# store-row-block.net
KiCad netlist of a schematic drawn in EAGLE
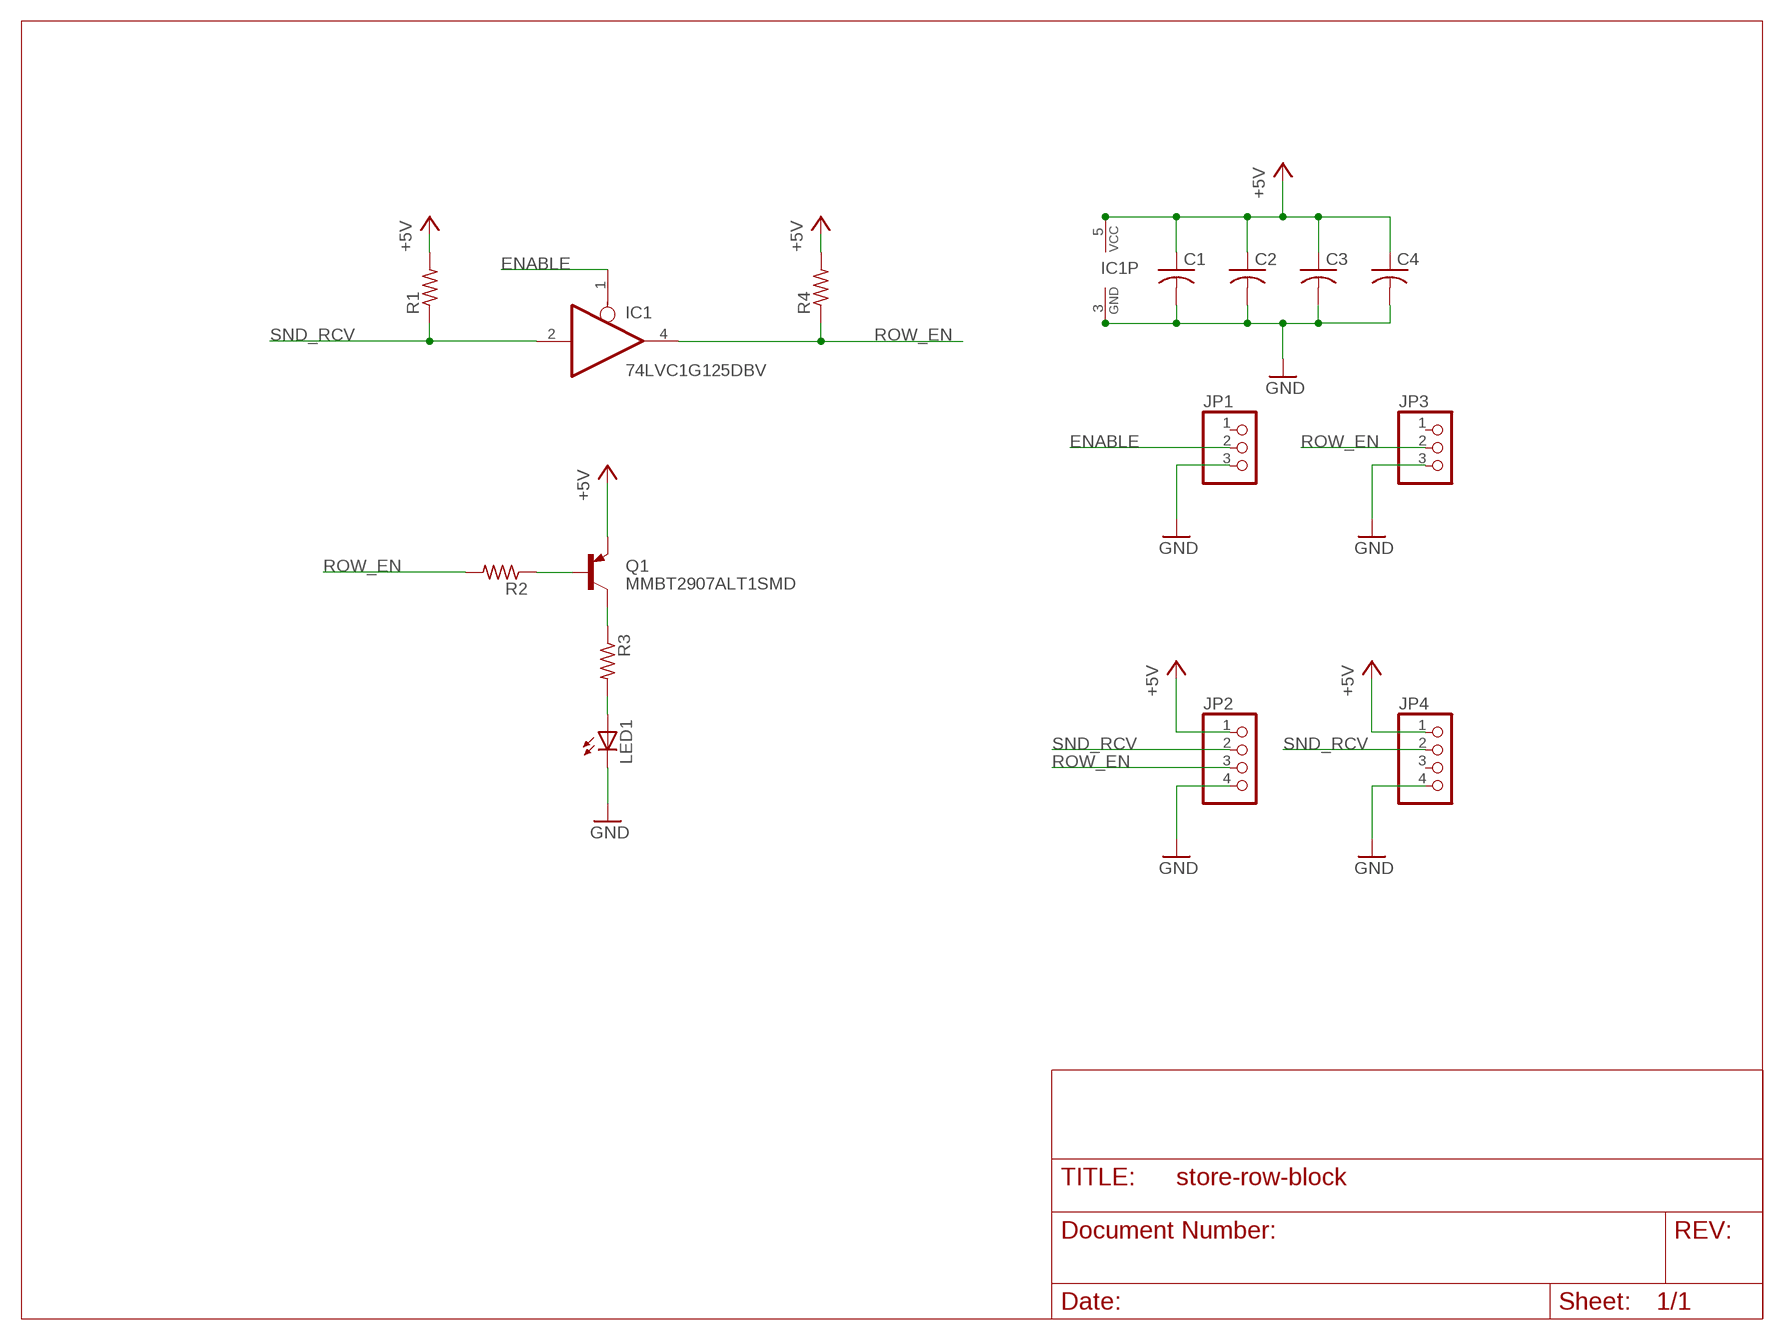
[diagram p0: schematic, sheet 1]

(export (version "E")
  (design (tool "Eeschema 10.0.6"))
  (components
    (comp (ref "C1")
      (value "C-USC0805")
      (footprint "eagle-import:C0805")
      (libsource (lib "eagle-import") (part "C-USC0805"))
    )
    (comp (ref "C2")
      (value "C-USC0805")
      (footprint "eagle-import:C0805")
      (libsource (lib "eagle-import") (part "C-USC0805"))
    )
    (comp (ref "C3")
      (value "C-USC0805")
      (footprint "eagle-import:C0805")
      (libsource (lib "eagle-import") (part "C-USC0805"))
    )
    (comp (ref "C4")
      (value "C-USC0805")
      (footprint "eagle-import:C0805")
      (libsource (lib "eagle-import") (part "C-USC0805"))
    )
    (comp (ref "IC1")
      (value "74LVC1G125DBV")
      (footprint "eagle-import:SOT23-5")
      (libsource (lib "eagle-import") (part "741G125DBVLVC"))
    )
    (comp (ref "JP1")
      (value "PINHD-1X3")
      (footprint "eagle-import:1X03")
      (libsource (lib "eagle-import") (part "PINHD-1X3"))
    )
    (comp (ref "JP2")
      (value "PINHD-1X4")
      (footprint "eagle-import:1X04")
      (libsource (lib "eagle-import") (part "PINHD-1X4"))
    )
    (comp (ref "JP3")
      (value "PINHD-1X3")
      (footprint "eagle-import:1X03")
      (libsource (lib "eagle-import") (part "PINHD-1X3"))
    )
    (comp (ref "JP4")
      (value "PINHD-1X4")
      (footprint "eagle-import:1X04")
      (libsource (lib "eagle-import") (part "PINHD-1X4"))
    )
    (comp (ref "LED1")
      (value "LEDCHIP-LED0805")
      (footprint "eagle-import:CHIP-LED0805")
      (libsource (lib "eagle-import") (part "LEDCHIP-LED0805"))
    )
    (comp (ref "Q1")
      (value "MMBT2907ALT1SMD")
      (footprint "eagle-import:SOT23-BEC")
      (libsource (lib "eagle-import") (part "MMBT2907SMDALT1"))
    )
    (comp (ref "R1")
      (value "R-US_R0805")
      (footprint "eagle-import:R0805")
      (libsource (lib "eagle-import") (part "R-US_R0805"))
    )
    (comp (ref "R2")
      (value "R-US_R0805")
      (footprint "eagle-import:R0805")
      (libsource (lib "eagle-import") (part "R-US_R0805"))
    )
    (comp (ref "R3")
      (value "R-US_R0805")
      (footprint "eagle-import:R0805")
      (libsource (lib "eagle-import") (part "R-US_R0805"))
    )
    (comp (ref "R4")
      (value "R-US_R0805")
      (footprint "eagle-import:R0805")
      (libsource (lib "eagle-import") (part "R-US_R0805"))
    )
  )
  (nets
    (net (code "1") (name "+5V") (class "Default")
      (node (ref "C1") (pin "1") (pinfunction "1_1") (pintype "passive"))
      (node (ref "C2") (pin "1") (pinfunction "1_1") (pintype "passive"))
      (node (ref "C3") (pin "1") (pinfunction "1_1") (pintype "passive"))
      (node (ref "C4") (pin "1") (pinfunction "1_1") (pintype "passive"))
      (node (ref "IC1") (pin "5") (pinfunction "VCC_5") (pintype "power_in"))
      (node (ref "JP2") (pin "1") (pinfunction "1_1") (pintype "passive"))
      (node (ref "JP4") (pin "1") (pinfunction "1_1") (pintype "passive"))
      (node (ref "Q1") (pin "E") (pinfunction "E_E") (pintype "passive"))
      (node (ref "R1") (pin "2") (pinfunction "2_2") (pintype "passive"))
      (node (ref "R4") (pin "2") (pinfunction "2_2") (pintype "passive"))
    )
    (net (code "2") (name "/ENABLE") (class "Default")
      (node (ref "IC1") (pin "1") (pinfunction "OE_1") (pintype "input"))
      (node (ref "JP1") (pin "2") (pinfunction "2_2") (pintype "passive"))
    )
    (net (code "3") (name "/ROW_EN") (class "Default")
      (node (ref "IC1") (pin "4") (pinfunction "O_4") (pintype "tri_state"))
      (node (ref "JP2") (pin "3") (pinfunction "3_3") (pintype "passive"))
      (node (ref "JP3") (pin "2") (pinfunction "2_2") (pintype "passive"))
      (node (ref "R2") (pin "2") (pinfunction "2_2") (pintype "passive"))
      (node (ref "R4") (pin "1") (pinfunction "1_1") (pintype "passive"))
    )
    (net (code "4") (name "/SND_RCV") (class "Default")
      (node (ref "IC1") (pin "2") (pinfunction "I_2") (pintype "input"))
      (node (ref "JP2") (pin "2") (pinfunction "2_2") (pintype "passive"))
      (node (ref "JP4") (pin "2") (pinfunction "2_2") (pintype "passive"))
      (node (ref "R1") (pin "1") (pinfunction "1_1") (pintype "passive"))
    )
    (net (code "5") (name "GND") (class "Default")
      (node (ref "C1") (pin "2") (pinfunction "2_2") (pintype "passive"))
      (node (ref "C2") (pin "2") (pinfunction "2_2") (pintype "passive"))
      (node (ref "C3") (pin "2") (pinfunction "2_2") (pintype "passive"))
      (node (ref "C4") (pin "2") (pinfunction "2_2") (pintype "passive"))
      (node (ref "IC1") (pin "3") (pinfunction "GND_3") (pintype "power_in"))
      (node (ref "JP1") (pin "3") (pinfunction "3_3") (pintype "passive"))
      (node (ref "JP2") (pin "4") (pinfunction "4_4") (pintype "passive"))
      (node (ref "JP3") (pin "3") (pinfunction "3_3") (pintype "passive"))
      (node (ref "JP4") (pin "4") (pinfunction "4_4") (pintype "passive"))
      (node (ref "LED1") (pin "C") (pinfunction "C_C") (pintype "passive"))
    )
    (net (code "6") (name "Net-(LED1-PadA)") (class "Default")
      (node (ref "LED1") (pin "A") (pinfunction "A_A") (pintype "passive"))
      (node (ref "R3") (pin "2") (pinfunction "2_2") (pintype "passive"))
    )
    (net (code "7") (name "Net-(Q1-PadB)") (class "Default")
      (node (ref "Q1") (pin "B") (pinfunction "B_B") (pintype "passive"))
      (node (ref "R2") (pin "1") (pinfunction "1_1") (pintype "passive"))
    )
    (net (code "8") (name "Net-(Q1-PadC)") (class "Default")
      (node (ref "Q1") (pin "C") (pinfunction "C_C") (pintype "passive"))
      (node (ref "R3") (pin "1") (pinfunction "1_1") (pintype "passive"))
    )
    (net (code "9") (name "unconnected-(JP1-Pad1)") (class "Default")
      (node (ref "JP1") (pin "1") (pinfunction "1_1") (pintype "passive"))
    )
    (net (code "10") (name "unconnected-(JP3-Pad1)") (class "Default")
      (node (ref "JP3") (pin "1") (pinfunction "1_1") (pintype "passive"))
    )
    (net (code "11") (name "unconnected-(JP4-Pad3)") (class "Default")
      (node (ref "JP4") (pin "3") (pinfunction "3_3") (pintype "passive"))
    )
  )
)
